# B45100557C.net
KiCad netlist of a schematic drawn in Altium Designer
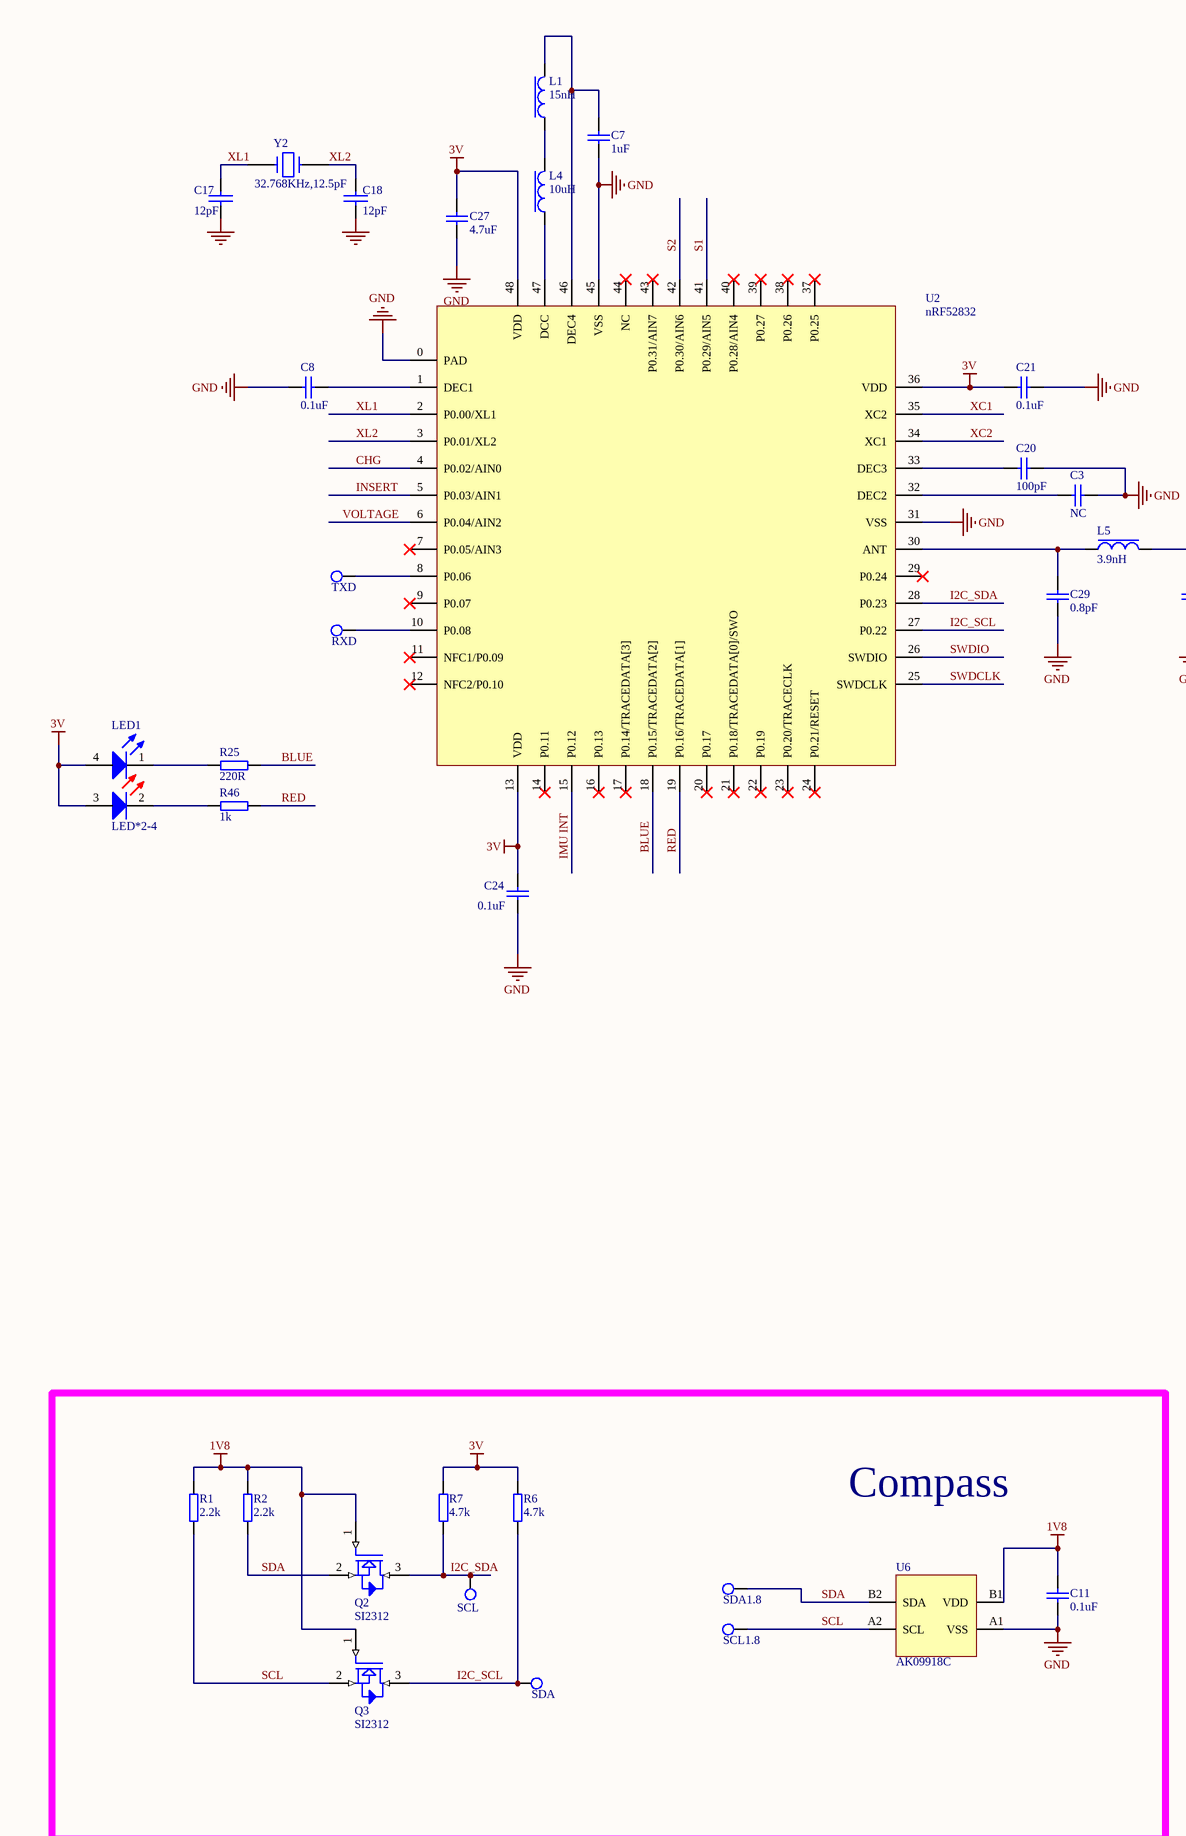
[diagram p0: B45100557C.SCHDOC, left]
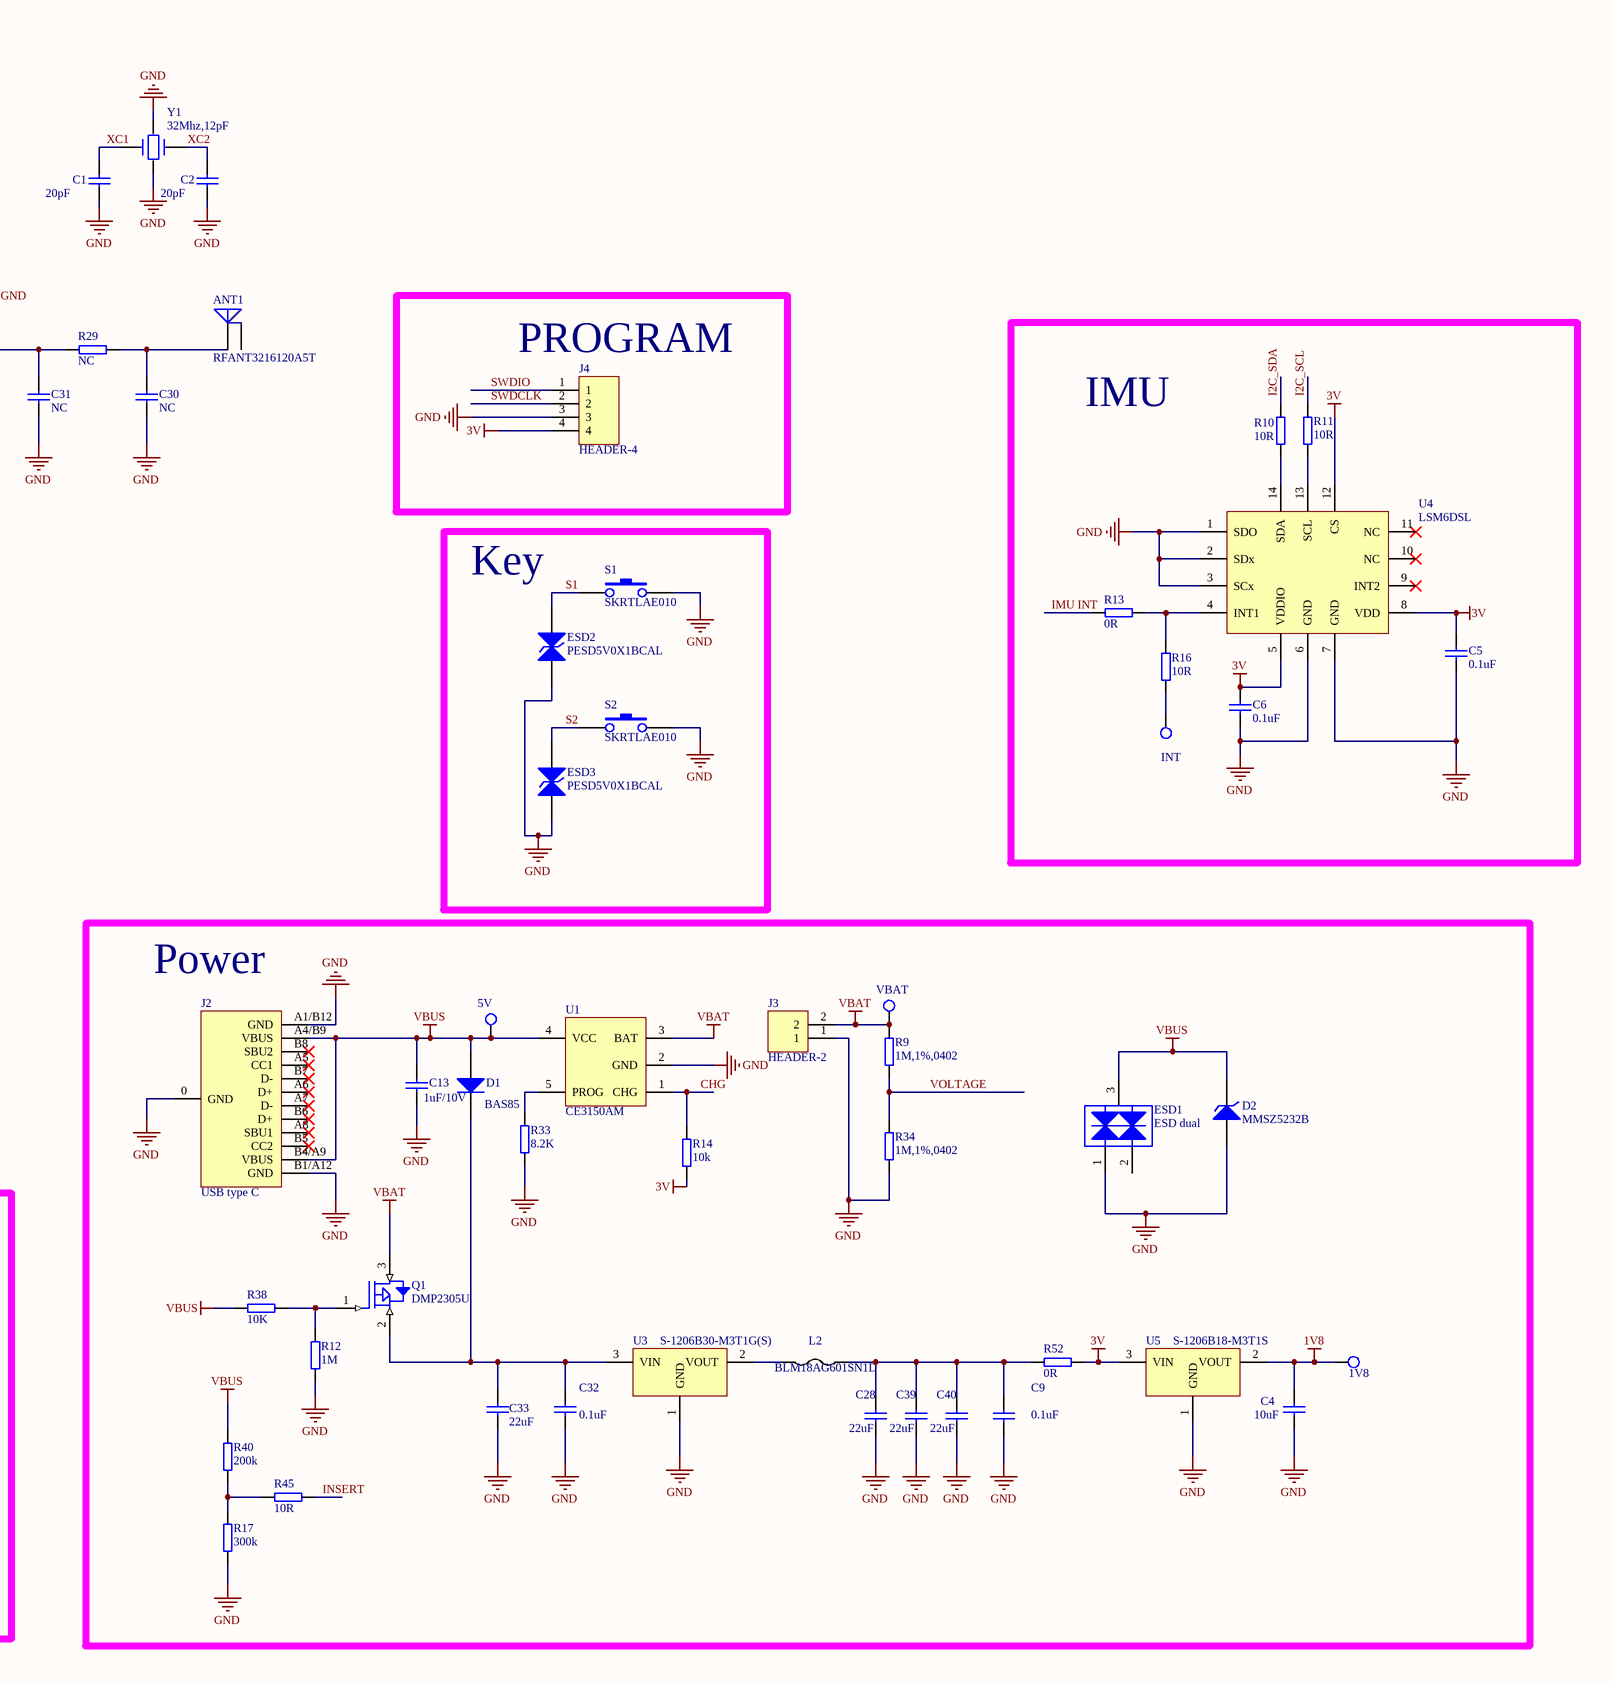
[diagram p1: B45100557C.SCHDOC, right]

(export (version "E")
  (design (tool "Eeschema 10.0.6"))
  (components
    (comp (ref "1V8") (value "TAP") (footprint "TS-1.0") (libsource (lib "dusun01-SCH") (part "TAP")))
    (comp (ref "5V") (value "TAP") (footprint "TS-1.0") (libsource (lib "dusun01-SCH") (part "TAP")))
    (comp (ref "ANT1")
      (value "RFANT3216120A5T")
      (footprint "RFANT3216120A1T")
      (libsource (lib "dusun01-SCH") (part "ANTENNA"))
    )
    (comp (ref "C1") (value "20pF") (footprint "C-0402") (libsource (lib "dusun01-SCH") (part "CAP")))
    (comp (ref "C2") (value "20pF") (footprint "C-0402") (libsource (lib "dusun01-SCH") (part "CAP")))
    (comp (ref "C3") (value "NC") (footprint "C-0402") (libsource (lib "dusun01-SCH") (part "CAP")))
    (comp (ref "C4") (value "10uF") (footprint "C-0603") (libsource (lib "dusun01-SCH") (part "CAP")))
    (comp (ref "C5")
      (value "0.1uF")
      (footprint "C-0402")
      (description "capacitor 27 pF NPO , +/- 2 %, SMD case 0603")
      (fields
        (field (name "MANUFACTURER") "Generic Components")
        (field (name "PUBLISHER") "Altium Hobart Technology Centre")
      )
      (libsource (lib "Miscellaneous Devices") (part "Cap"))
    )
    (comp (ref "C6")
      (value "0.1uF")
      (footprint "C-0402")
      (description "capacitor 27 pF NPO , +/- 2 %, SMD case 0603")
      (fields
        (field (name "MANUFACTURER") "Generic Components")
        (field (name "PUBLISHER") "Altium Hobart Technology Centre")
      )
      (libsource (lib "Miscellaneous Devices") (part "Cap"))
    )
    (comp (ref "C7") (value "1uF") (footprint "C-0402") (libsource (lib "dusun01-SCH") (part "CAP")))
    (comp (ref "C8") (value "0.1uF") (footprint "C-0402") (libsource (lib "dusun01-SCH") (part "CAP")))
    (comp (ref "C9") (value "0.1uF") (footprint "C-0402") (libsource (lib "dusun01-SCH") (part "CAP")))
    (comp (ref "C11")
      (value "0.1uF")
      (footprint "C-0402")
      (description "capacitor 27 pF NPO , +/- 2 %, SMD case 0603")
      (fields
        (field (name "MANUFACTURER") "Generic Components")
        (field (name "PUBLISHER") "Altium Hobart Technology Centre")
      )
      (libsource (lib "Miscellaneous Devices") (part "Cap"))
    )
    (comp (ref "C13") (value "1uF/10V") (footprint "C-0402") (libsource (lib "dusun01-SCH") (part "CAP")))
    (comp (ref "C17")
      (value "12pF")
      (footprint "dusun01-pcb:C-0402")
      (description "Capacitor")
      (libsource (lib "*") (part "CAP"))
    )
    (comp (ref "C18")
      (value "12pF")
      (footprint "dusun01-pcb:C-0402")
      (description "Capacitor")
      (libsource (lib "*") (part "CAP"))
    )
    (comp (ref "C20") (value "100pF") (footprint "C-0402") (libsource (lib "dusun01-SCH") (part "CAP")))
    (comp (ref "C21") (value "0.1uF") (footprint "C-0402") (libsource (lib "dusun01-SCH") (part "CAP")))
    (comp (ref "C24") (value "0.1uF") (footprint "C-0402") (libsource (lib "dusun01-SCH") (part "CAP")))
    (comp (ref "C27") (value "4.7uF") (footprint "C-0603") (libsource (lib "dusun01-SCH") (part "CAP")))
    (comp (ref "C28") (value "22uF") (footprint "C-0805") (libsource (lib "dusun01-SCH") (part "CAP")))
    (comp (ref "C29") (value "0.8pF") (footprint "C-0402") (libsource (lib "dusun01-SCH") (part "CAP")))
    (comp (ref "C30") (value "NC") (footprint "C-0402") (libsource (lib "dusun01-SCH") (part "CAP")))
    (comp (ref "C31") (value "NC") (footprint "C-0402") (libsource (lib "dusun01-SCH") (part "CAP")))
    (comp (ref "C32") (value "0.1uF") (footprint "C-0402") (libsource (lib "dusun01-SCH") (part "CAP")))
    (comp (ref "C33") (value "22uF") (footprint "dusun01-pcb:C-0805") (libsource (lib "") (part "CAP_1")))
    (comp (ref "C39") (value "22uF") (footprint "C-0805") (libsource (lib "dusun01-SCH") (part "CAP")))
    (comp (ref "C40") (value "22uF") (footprint "C-0805") (libsource (lib "dusun01-SCH") (part "CAP")))
    (comp (ref "D1") (value "BAS85") (footprint "SOD-80") (libsource (lib "dusun01-SCH") (part "DIODE")))
    (comp (ref "D2") (value "MMSZ5232B") (footprint "sod-123") (libsource (lib "dusun01-SCH") (part "ZENER")))
    (comp (ref "ESD1")
      (value "ESD dual")
      (footprint "SOT-23")
      (libsource (lib "dusun01-SCH") (part "ESD dual"))
    )
    (comp (ref "ESD2")
      (value "PESD5V0X1BCAL")
      (footprint "R-0402")
      (libsource (lib "dusun01-SCH") (part "ESD"))
    )
    (comp (ref "ESD3")
      (value "PESD5V0X1BCAL")
      (footprint "R-0402")
      (libsource (lib "dusun01-SCH") (part "ESD"))
    )
    (comp (ref "INT") (value "TAP") (footprint "TS-1.0") (libsource (lib "dusun01-SCH") (part "TAP")))
    (comp (ref "J2")
      (value "USB type C")
      (footprint "USB type C")
      (libsource (lib "dusun01-SCH") (part "USB type C"))
    )
    (comp (ref "J3")
      (value "HEADER-2")
      (footprint "1.25T-2AWB")
      (libsource (lib "dusun01-SCH") (part "HEADER-2"))
    )
    (comp (ref "J4")
      (value "HEADER-4")
      (footprint "PH-4-2.54-1")
      (libsource (lib "dusun01-SCH") (part "HEADER-4"))
    )
    (comp (ref "L1") (value "15nH") (footprint "R-0402") (libsource (lib "dusun01-SCH") (part "INDUCTOR")))
    (comp (ref "L2")
      (value "BLM18AG601SN1D")
      (footprint "dusun01-pcb:R-0603")
      (libsource (lib "*") (part "Inductance"))
    )
    (comp (ref "L4")
      (value "10uH")
      (footprint "dusun02-pcb:R-0805")
      (libsource (lib "dusun01-SCH") (part "INDUCTOR"))
    )
    (comp (ref "L5") (value "3.9nH") (footprint "R-0402") (libsource (lib "dusun01-SCH") (part "INDUCTOR")))
    (comp (ref "LED1")
      (value "LED*2-4")
      (footprint "A-SP1942R6B1C-A01-2T")
      (libsource (lib "dusun01-SCH") (part "LED*2-4"))
    )
    (comp (ref "Q1")
      (value "DMP2305U")
      (footprint "SOT-23")
      (libsource (lib "dusun01-SCH") (part "MOSFET P"))
    )
    (comp (ref "Q2") (value "SI2312") (footprint "SOT-23") (libsource (lib "dusun01-SCH") (part "MOSFET N")))
    (comp (ref "Q3") (value "SI2312") (footprint "SOT-23") (libsource (lib "dusun01-SCH") (part "MOSFET N")))
    (comp (ref "R1") (value "2.2k") (footprint "R-0402") (libsource (lib "dusun01-SCH") (part "RES")))
    (comp (ref "R2") (value "2.2k") (footprint "R-0402") (libsource (lib "dusun01-SCH") (part "RES")))
    (comp (ref "R6") (value "4.7k") (footprint "R-0402") (libsource (lib "dusun01-SCH") (part "RES")))
    (comp (ref "R7") (value "4.7k") (footprint "R-0402") (libsource (lib "dusun01-SCH") (part "RES")))
    (comp (ref "R9") (value "1M,1%,0402") (footprint "R-0402") (libsource (lib "dusun01-SCH") (part "RES")))
    (comp (ref "R10") (value "10R") (footprint "R-0402") (libsource (lib "dusun01-SCH") (part "RES")))
    (comp (ref "R11") (value "10R") (footprint "R-0402") (libsource (lib "dusun01-SCH") (part "RES")))
    (comp (ref "R12") (value "1M") (footprint "R-0402") (libsource (lib "dusun01-SCH") (part "RES")))
    (comp (ref "R13") (value "0R") (footprint "R-0402") (libsource (lib "dusun01-SCH") (part "RES")))
    (comp (ref "R14") (value "10k") (footprint "R-0402") (libsource (lib "dusun01-SCH") (part "RES")))
    (comp (ref "R16") (value "10R") (footprint "R-0402") (libsource (lib "dusun01-SCH") (part "RES")))
    (comp (ref "R17") (value "300k") (footprint "R-0402") (libsource (lib "dusun01-SCH") (part "RES")))
    (comp (ref "R25") (value "220R") (footprint "R-0402") (libsource (lib "dusun01-SCH") (part "RES")))
    (comp (ref "R29") (value "NC") (footprint "R-0402") (libsource (lib "dusun01-SCH") (part "RES")))
    (comp (ref "R33") (value "8.2K") (footprint "R-0402") (libsource (lib "dusun01-SCH") (part "RES")))
    (comp (ref "R34") (value "1M,1%,0402") (footprint "R-0402") (libsource (lib "dusun01-SCH") (part "RES")))
    (comp (ref "R38") (value "10K") (footprint "R-0402") (libsource (lib "dusun01-SCH") (part "RES")))
    (comp (ref "R40") (value "200k") (footprint "R-0402") (libsource (lib "dusun01-SCH") (part "RES")))
    (comp (ref "R45") (value "10R") (footprint "R-0402") (libsource (lib "dusun01-SCH") (part "RES")))
    (comp (ref "R46") (value "1k") (footprint "R-0402") (libsource (lib "dusun01-SCH") (part "RES")))
    (comp (ref "R52") (value "0R") (footprint "R-0603") (libsource (lib "dusun01-SCH") (part "RES")))
    (comp (ref "RXD") (value "TAP") (footprint "TS-1.0") (libsource (lib "dusun01-SCH") (part "TAP")))
    (comp (ref "S1") (value "SKRTLAE010") (footprint "SKRTLAE010") (libsource (lib "dusun") (part "SW-PB")))
    (comp (ref "S2") (value "SKRTLAE010") (footprint "SKRTLAE010") (libsource (lib "dusun") (part "SW-PB")))
    (comp (ref "SCL") (value "TAP") (footprint "TS-1.0") (libsource (lib "dusun01-SCH") (part "TAP")))
    (comp (ref "SCL1.8") (value "TAP") (footprint "TS-1.0") (libsource (lib "dusun01-SCH") (part "TAP")))
    (comp (ref "SDA") (value "TAP") (footprint "TS-1.0") (libsource (lib "dusun01-SCH") (part "TAP")))
    (comp (ref "SDA1.8") (value "TAP") (footprint "TS-1.0") (libsource (lib "dusun01-SCH") (part "TAP")))
    (comp (ref "TXD") (value "TAP") (footprint "TS-1.0") (libsource (lib "dusun01-SCH") (part "TAP")))
    (comp (ref "U1")
      (value "CE3150AM")
      (footprint "SOT-23-5")
      (libsource (lib "dusun01-SCH") (part "CE3150AM"))
    )
    (comp (ref "U2")
      (value "nRF52832")
      (footprint "QFN-48-6*6-0.4")
      (libsource (lib "dusun01-SCH") (part "nRF52832"))
    )
    (comp (ref "U3")
      (value "S-1206B30-M3T1G(S)")
      (footprint "SOT-23")
      (libsource (lib "dusun01-SCH") (part "S-1206BXX"))
    )
    (comp (ref "U4") (value "LSM6DSL") (footprint "LGA14") (libsource (lib "dusun01-SCH") (part "LSM6DSL")))
    (comp (ref "U5")
      (value "S-1206B18-M3T1S")
      (footprint "SOT-23")
      (libsource (lib "dusun01-SCH") (part "S-1206BXX"))
    )
    (comp (ref "U6")
      (value "AK09918C")
      (footprint "AK09918C")
      (libsource (lib "dusun01-SCH") (part "AK09918C"))
    )
    (comp (ref "VBAT") (value "TAP") (footprint "TS-1.0") (libsource (lib "dusun01-SCH") (part "TAP")))
    (comp (ref "Y1")
      (value "32Mhz,12pF")
      (footprint "XD3225-1-12M-125M")
      (libsource (lib "dusun01-SCH") (part "CRYSTAL4"))
    )
    (comp (ref "Y2")
      (value "32.768KHz,12.5pF")
      (footprint "32.768Khz-3215")
      (libsource (lib "dusun01-SCH") (part "CRYSTAL2"))
    )
  )
  (nets
    (net (code "1") (name "/BLUE") (class "Default")
      (node (ref "R25") (pin "1") (pinfunction "1_1") (pintype "passive"))
      (node (ref "U2") (pin "18") (pinfunction "P0.15/TRACEDATA[2]_18") (pintype "passive"))
    )
    (net (code "2") (name "/CHG") (class "Default")
      (node (ref "R14") (pin "2") (pinfunction "2_2") (pintype "passive"))
      (node (ref "U1") (pin "1") (pinfunction "CHG_1") (pintype "passive"))
      (node (ref "U2") (pin "4") (pinfunction "P0.02/AIN0_4") (pintype "passive"))
    )
    (net (code "3") (name "/I2C_SCL") (class "Default")
      (node (ref "Q3") (pin "3") (pinfunction "D_3") (pintype "input"))
      (node (ref "R11") (pin "2") (pinfunction "2_2") (pintype "passive"))
      (node (ref "R6") (pin "2") (pinfunction "2_2") (pintype "passive"))
      (node (ref "SDA") (pin "1") (pinfunction "1_1") (pintype "passive"))
      (node (ref "U2") (pin "27") (pinfunction "P0.22_27") (pintype "passive"))
    )
    (net (code "4") (name "/I2C_SDA") (class "Default")
      (node (ref "Q2") (pin "3") (pinfunction "D_3") (pintype "input"))
      (node (ref "R10") (pin "2") (pinfunction "2_2") (pintype "passive"))
      (node (ref "R7") (pin "2") (pinfunction "2_2") (pintype "passive"))
      (node (ref "SCL") (pin "1") (pinfunction "1_1") (pintype "passive"))
      (node (ref "U2") (pin "28") (pinfunction "P0.23_28") (pintype "passive"))
    )
    (net (code "5") (name "/IMU INT") (class "Default")
      (node (ref "R13") (pin "1") (pinfunction "1_1") (pintype "passive"))
      (node (ref "U2") (pin "15") (pinfunction "P0.12_15") (pintype "passive"))
    )
    (net (code "6") (name "/INSERT") (class "Default")
      (node (ref "R45") (pin "1") (pinfunction "1_1") (pintype "passive"))
      (node (ref "U2") (pin "5") (pinfunction "P0.03/AIN1_5") (pintype "passive"))
    )
    (net (code "7") (name "/RED") (class "Default")
      (node (ref "R46") (pin "1") (pinfunction "1_1") (pintype "passive"))
      (node (ref "U2") (pin "19") (pinfunction "P0.16/TRACEDATA[1]_19") (pintype "passive"))
    )
    (net (code "8") (name "/S1") (class "Default")
      (node (ref "ESD2") (pin "2") (pinfunction "2_2") (pintype "passive"))
      (node (ref "S1") (pin "2") (pinfunction "2_2") (pintype "passive"))
      (node (ref "U2") (pin "41") (pinfunction "P0.29/AIN5_41") (pintype "passive"))
    )
    (net (code "9") (name "/S2") (class "Default")
      (node (ref "ESD3") (pin "2") (pinfunction "2_2") (pintype "passive"))
      (node (ref "S2") (pin "2") (pinfunction "2_2") (pintype "passive"))
      (node (ref "U2") (pin "42") (pinfunction "P0.30/AIN6_42") (pintype "passive"))
    )
    (net (code "10") (name "/SCL") (class "Default")
      (node (ref "Q3") (pin "2") (pinfunction "S_2") (pintype "input"))
      (node (ref "R1") (pin "2") (pinfunction "2_2") (pintype "passive"))
      (node (ref "SCL1.8") (pin "1") (pinfunction "1_1") (pintype "passive"))
      (node (ref "U6") (pin "A2") (pinfunction "SCL_A2") (pintype "passive"))
    )
    (net (code "11") (name "/SDA") (class "Default")
      (node (ref "Q2") (pin "2") (pinfunction "S_2") (pintype "input"))
      (node (ref "R2") (pin "2") (pinfunction "2_2") (pintype "passive"))
      (node (ref "SDA1.8") (pin "1") (pinfunction "1_1") (pintype "passive"))
      (node (ref "U6") (pin "B2") (pinfunction "SDA_B2") (pintype "passive"))
    )
    (net (code "12") (name "/SWDCLK") (class "Default")
      (node (ref "J4") (pin "2") (pinfunction "2_2") (pintype "passive"))
      (node (ref "U2") (pin "25") (pinfunction "SWDCLK_25") (pintype "passive"))
    )
    (net (code "13") (name "/SWDIO") (class "Default")
      (node (ref "J4") (pin "1") (pinfunction "1_1") (pintype "passive"))
      (node (ref "U2") (pin "26") (pinfunction "SWDIO_26") (pintype "passive"))
    )
    (net (code "14") (name "/VOLTAGE") (class "Default")
      (node (ref "R34") (pin "2") (pinfunction "2_2") (pintype "passive"))
      (node (ref "R9") (pin "1") (pinfunction "1_1") (pintype "passive"))
      (node (ref "U2") (pin "6") (pinfunction "P0.04/AIN2_6") (pintype "passive"))
    )
    (net (code "15") (name "/XC1") (class "Default")
      (node (ref "C1") (pin "1") (pinfunction "1_1") (pintype "passive"))
      (node (ref "U2") (pin "35") (pinfunction "XC2_35") (pintype "passive"))
      (node (ref "Y1") (pin "1") (pinfunction "1_1") (pintype "passive"))
    )
    (net (code "16") (name "/XC2") (class "Default")
      (node (ref "C2") (pin "1") (pinfunction "1_1") (pintype "passive"))
      (node (ref "U2") (pin "34") (pinfunction "XC1_34") (pintype "passive"))
      (node (ref "Y1") (pin "2") (pinfunction "2_2") (pintype "passive"))
    )
    (net (code "17") (name "/XL1") (class "Default")
      (node (ref "C17") (pin "1") (pinfunction "1_1") (pintype "passive"))
      (node (ref "U2") (pin "2") (pinfunction "P0.00/XL1_2") (pintype "passive"))
      (node (ref "Y2") (pin "1") (pinfunction "1_1") (pintype "passive"))
    )
    (net (code "18") (name "/XL2") (class "Default")
      (node (ref "C18") (pin "1") (pinfunction "1_1") (pintype "passive"))
      (node (ref "U2") (pin "3") (pinfunction "P0.01/XL2_3") (pintype "passive"))
      (node (ref "Y2") (pin "2") (pinfunction "2_2") (pintype "passive"))
    )
    (net (code "19") (name "1V8") (class "Default")
      (node (ref "1V8") (pin "1") (pinfunction "1_1") (pintype "passive"))
      (node (ref "C11") (pin "1") (pinfunction "1_1") (pintype "passive"))
      (node (ref "C4") (pin "1") (pinfunction "1_1") (pintype "passive"))
      (node (ref "Q2") (pin "1") (pinfunction "G_1") (pintype "input"))
      (node (ref "Q3") (pin "1") (pinfunction "G_1") (pintype "input"))
      (node (ref "R1") (pin "1") (pinfunction "1_1") (pintype "passive"))
      (node (ref "R2") (pin "1") (pinfunction "1_1") (pintype "passive"))
      (node (ref "U5") (pin "2") (pinfunction "VOUT_2") (pintype "passive"))
      (node (ref "U6") (pin "B1") (pinfunction "VDD_B1") (pintype "passive"))
    )
    (net (code "20") (name "3V") (class "Default")
      (node (ref "C21") (pin "1") (pinfunction "1_1") (pintype "passive"))
      (node (ref "C24") (pin "1") (pinfunction "1_1") (pintype "passive"))
      (node (ref "C27") (pin "1") (pinfunction "1_1") (pintype "passive"))
      (node (ref "C5") (pin "1") (pinfunction "1_1") (pintype "passive"))
      (node (ref "C6") (pin "1") (pinfunction "1_1") (pintype "passive"))
      (node (ref "J4") (pin "4") (pinfunction "4_4") (pintype "passive"))
      (node (ref "LED1") (pin "3") (pinfunction "3_3") (pintype "passive"))
      (node (ref "LED1") (pin "4") (pinfunction "4_4") (pintype "passive"))
      (node (ref "R14") (pin "1") (pinfunction "1_1") (pintype "passive"))
      (node (ref "R52") (pin "1") (pinfunction "1_1") (pintype "passive"))
      (node (ref "R6") (pin "1") (pinfunction "1_1") (pintype "passive"))
      (node (ref "R7") (pin "1") (pinfunction "1_1") (pintype "passive"))
      (node (ref "U2") (pin "13") (pinfunction "VDD_13") (pintype "passive"))
      (node (ref "U2") (pin "36") (pinfunction "VDD_36") (pintype "passive"))
      (node (ref "U2") (pin "48") (pinfunction "VDD_48") (pintype "passive"))
      (node (ref "U4") (pin "12") (pinfunction "CS_12") (pintype "passive"))
      (node (ref "U4") (pin "5") (pinfunction "VDDIO_5") (pintype "passive"))
      (node (ref "U4") (pin "8") (pinfunction "VDD_8") (pintype "passive"))
      (node (ref "U5") (pin "3") (pinfunction "VIN_3") (pintype "passive"))
    )
    (net (code "21") (name "GND") (class "Default")
      (node (ref "C1") (pin "2") (pinfunction "2_2") (pintype "passive"))
      (node (ref "C11") (pin "2") (pinfunction "2_2") (pintype "passive"))
      (node (ref "C13") (pin "2") (pinfunction "2_2") (pintype "passive"))
      (node (ref "C17") (pin "2") (pinfunction "2_2") (pintype "passive"))
      (node (ref "C18") (pin "2") (pinfunction "2_2") (pintype "passive"))
      (node (ref "C2") (pin "2") (pinfunction "2_2") (pintype "passive"))
      (node (ref "C20") (pin "2") (pinfunction "2_2") (pintype "passive"))
      (node (ref "C21") (pin "2") (pinfunction "2_2") (pintype "passive"))
      (node (ref "C24") (pin "2") (pinfunction "2_2") (pintype "passive"))
      (node (ref "C27") (pin "2") (pinfunction "2_2") (pintype "passive"))
      (node (ref "C28") (pin "2") (pinfunction "2_2") (pintype "passive"))
      (node (ref "C29") (pin "2") (pinfunction "2_2") (pintype "passive"))
      (node (ref "C3") (pin "2") (pinfunction "2_2") (pintype "passive"))
      (node (ref "C30") (pin "2") (pinfunction "2_2") (pintype "passive"))
      (node (ref "C31") (pin "2") (pinfunction "2_2") (pintype "passive"))
      (node (ref "C32") (pin "2") (pinfunction "2_2") (pintype "passive"))
      (node (ref "C33") (pin "2") (pinfunction "2_2") (pintype "passive"))
      (node (ref "C39") (pin "2") (pinfunction "2_2") (pintype "passive"))
      (node (ref "C4") (pin "2") (pinfunction "2_2") (pintype "passive"))
      (node (ref "C40") (pin "2") (pinfunction "2_2") (pintype "passive"))
      (node (ref "C5") (pin "2") (pinfunction "2_2") (pintype "passive"))
      (node (ref "C6") (pin "2") (pinfunction "2_2") (pintype "passive"))
      (node (ref "C7") (pin "1") (pinfunction "1_1") (pintype "passive"))
      (node (ref "C8") (pin "1") (pinfunction "1_1") (pintype "passive"))
      (node (ref "C9") (pin "2") (pinfunction "2_2") (pintype "passive"))
      (node (ref "D2") (pin "1") (pinfunction "1_1") (pintype "passive"))
      (node (ref "ESD1") (pin "1") (pinfunction "1_1") (pintype "passive"))
      (node (ref "ESD2") (pin "1") (pinfunction "1_1") (pintype "passive"))
      (node (ref "ESD3") (pin "1") (pinfunction "1_1") (pintype "passive"))
      (node (ref "J2") (pin "0") (pinfunction "GND_0") (pintype "passive"))
      (node (ref "J2") (pin "A1/B12") (pinfunction "GND_A1/B12") (pintype "passive"))
      (node (ref "J2") (pin "B1/A12") (pinfunction "GND_B1/A12") (pintype "passive"))
      (node (ref "J3") (pin "1") (pinfunction "1_1") (pintype "passive"))
      (node (ref "J4") (pin "3") (pinfunction "3_3") (pintype "passive"))
      (node (ref "R12") (pin "1") (pinfunction "1_1") (pintype "passive"))
      (node (ref "R17") (pin "1") (pinfunction "1_1") (pintype "passive"))
      (node (ref "R33") (pin "1") (pinfunction "1_1") (pintype "passive"))
      (node (ref "R34") (pin "1") (pinfunction "1_1") (pintype "passive"))
      (node (ref "S1") (pin "1") (pinfunction "1_1") (pintype "passive"))
      (node (ref "S2") (pin "1") (pinfunction "1_1") (pintype "passive"))
      (node (ref "U1") (pin "2") (pinfunction "GND_2") (pintype "passive"))
      (node (ref "U2") (pin "0") (pinfunction "PAD_0") (pintype "passive"))
      (node (ref "U2") (pin "31") (pinfunction "VSS_31") (pintype "passive"))
      (node (ref "U2") (pin "45") (pinfunction "VSS_45") (pintype "passive"))
      (node (ref "U3") (pin "1") (pinfunction "GND_1") (pintype "passive"))
      (node (ref "U4") (pin "1") (pinfunction "SDO_1") (pintype "passive"))
      (node (ref "U4") (pin "2") (pinfunction "SDx_2") (pintype "passive"))
      (node (ref "U4") (pin "3") (pinfunction "SCx_3") (pintype "passive"))
      (node (ref "U4") (pin "6") (pinfunction "GND_6") (pintype "passive"))
      (node (ref "U4") (pin "7") (pinfunction "GND_7") (pintype "passive"))
      (node (ref "U5") (pin "1") (pinfunction "GND_1") (pintype "passive"))
      (node (ref "U6") (pin "A1") (pinfunction "VSS_A1") (pintype "passive"))
      (node (ref "Y1") (pin "3") (pinfunction "3_3") (pintype "passive"))
    )
    (net (code "22") (name "Net-(ANT1-Pad1)") (class "Default")
      (node (ref "ANT1") (pin "1") (pinfunction "1_1") (pintype "passive"))
      (node (ref "C30") (pin "1") (pinfunction "1_1") (pintype "passive"))
      (node (ref "R29") (pin "2") (pinfunction "2_2") (pintype "passive"))
    )
    (net (code "23") (name "Net-(C28-Pad1)") (class "Default")
      (node (ref "C28") (pin "1") (pinfunction "1_1") (pintype "passive"))
      (node (ref "C39") (pin "1") (pinfunction "1_1") (pintype "passive"))
      (node (ref "C40") (pin "1") (pinfunction "1_1") (pintype "passive"))
      (node (ref "C9") (pin "1") (pinfunction "1_1") (pintype "passive"))
      (node (ref "L2") (pin "1") (pintype "passive"))
      (node (ref "R52") (pin "2") (pinfunction "2_2") (pintype "passive"))
    )
    (net (code "24") (name "Net-(C31-Pad1)") (class "Default")
      (node (ref "C31") (pin "1") (pinfunction "1_1") (pintype "passive"))
      (node (ref "L5") (pin "2") (pinfunction "2_2") (pintype "passive"))
      (node (ref "R29") (pin "1") (pinfunction "1_1") (pintype "passive"))
    )
    (net (code "25") (name "Net-(INT-Pad1)") (class "Default")
      (node (ref "INT") (pin "1") (pinfunction "1_1") (pintype "passive"))
      (node (ref "R16") (pin "1") (pinfunction "1_1") (pintype "passive"))
    )
    (net (code "26") (name "Net-(L1-Pad1)") (class "Default")
      (node (ref "L1") (pin "1") (pinfunction "1_1") (pintype "passive"))
      (node (ref "L4") (pin "2") (pinfunction "2_2") (pintype "passive"))
    )
    (net (code "27") (name "Net-(LED1-Pad1)") (class "Default")
      (node (ref "LED1") (pin "1") (pinfunction "1_1") (pintype "passive"))
      (node (ref "R25") (pin "2") (pinfunction "2_2") (pintype "passive"))
    )
    (net (code "28") (name "Net-(LED1-Pad2)") (class "Default")
      (node (ref "LED1") (pin "2") (pinfunction "2_2") (pintype "passive"))
      (node (ref "R46") (pin "2") (pinfunction "2_2") (pintype "passive"))
    )
    (net (code "29") (name "Net-(Q1-G)") (class "Default")
      (node (ref "Q1") (pin "1") (pinfunction "G_1") (pintype "input"))
      (node (ref "R12") (pin "2") (pinfunction "2_2") (pintype "passive"))
      (node (ref "R38") (pin "1") (pinfunction "1_1") (pintype "passive"))
    )
    (net (code "30") (name "Net-(Q1-S)") (class "Default")
      (node (ref "C32") (pin "1") (pinfunction "1_1") (pintype "passive"))
      (node (ref "C33") (pin "1") (pinfunction "1_1") (pintype "passive"))
      (node (ref "D1") (pin "2") (pinfunction "2_2") (pintype "passive"))
      (node (ref "Q1") (pin "2") (pinfunction "S_2") (pintype "input"))
      (node (ref "U3") (pin "3") (pinfunction "VIN_3") (pintype "passive"))
    )
    (net (code "31") (name "Net-(R17-Pad2)") (class "Default")
      (node (ref "R17") (pin "2") (pinfunction "2_2") (pintype "passive"))
      (node (ref "R40") (pin "1") (pinfunction "1_1") (pintype "passive"))
      (node (ref "R45") (pin "2") (pinfunction "2_2") (pintype "passive"))
    )
    (net (code "32") (name "Net-(U1-PROG)") (class "Default")
      (node (ref "R33") (pin "2") (pinfunction "2_2") (pintype "passive"))
      (node (ref "U1") (pin "5") (pinfunction "PROG_5") (pintype "passive"))
    )
    (net (code "33") (name "Net-(U2-ANT)") (class "Default")
      (node (ref "C29") (pin "1") (pinfunction "1_1") (pintype "passive"))
      (node (ref "L5") (pin "1") (pinfunction "1_1") (pintype "passive"))
      (node (ref "U2") (pin "30") (pinfunction "ANT_30") (pintype "passive"))
    )
    (net (code "34") (name "Net-(U2-DCC)") (class "Default")
      (node (ref "L4") (pin "1") (pinfunction "1_1") (pintype "passive"))
      (node (ref "U2") (pin "47") (pinfunction "DCC_47") (pintype "passive"))
    )
    (net (code "35") (name "Net-(U2-DEC1)") (class "Default")
      (node (ref "C8") (pin "2") (pinfunction "2_2") (pintype "passive"))
      (node (ref "U2") (pin "1") (pinfunction "DEC1_1") (pintype "passive"))
    )
    (net (code "36") (name "Net-(U2-DEC2)") (class "Default")
      (node (ref "C3") (pin "1") (pinfunction "1_1") (pintype "passive"))
      (node (ref "U2") (pin "32") (pinfunction "DEC2_32") (pintype "passive"))
    )
    (net (code "37") (name "Net-(U2-DEC3)") (class "Default")
      (node (ref "C20") (pin "1") (pinfunction "1_1") (pintype "passive"))
      (node (ref "U2") (pin "33") (pinfunction "DEC3_33") (pintype "passive"))
    )
    (net (code "38") (name "Net-(U2-DEC4)") (class "Default")
      (node (ref "C7") (pin "2") (pinfunction "2_2") (pintype "passive"))
      (node (ref "L1") (pin "2") (pinfunction "2_2") (pintype "passive"))
      (node (ref "U2") (pin "46") (pinfunction "DEC4_46") (pintype "passive"))
    )
    (net (code "39") (name "Net-(U2-P0.06)") (class "Default")
      (node (ref "TXD") (pin "1") (pinfunction "1_1") (pintype "passive"))
      (node (ref "U2") (pin "8") (pinfunction "P0.06_8") (pintype "passive"))
    )
    (net (code "40") (name "Net-(U2-P0.08)") (class "Default")
      (node (ref "RXD") (pin "1") (pinfunction "1_1") (pintype "passive"))
      (node (ref "U2") (pin "10") (pinfunction "P0.08_10") (pintype "passive"))
    )
    (net (code "41") (name "Net-(U3-VOUT)") (class "Default")
      (node (ref "L2") (pin "2") (pintype "passive"))
      (node (ref "U3") (pin "2") (pinfunction "VOUT_2") (pintype "passive"))
    )
    (net (code "42") (name "Net-(U4-INT1)") (class "Default")
      (node (ref "R13") (pin "2") (pinfunction "2_2") (pintype "passive"))
      (node (ref "R16") (pin "2") (pinfunction "2_2") (pintype "passive"))
      (node (ref "U4") (pin "4") (pinfunction "INT1_4") (pintype "passive"))
    )
    (net (code "43") (name "Net-(U4-SCL)") (class "Default")
      (node (ref "R11") (pin "1") (pinfunction "1_1") (pintype "passive"))
      (node (ref "U4") (pin "13") (pinfunction "SCL_13") (pintype "passive"))
    )
    (net (code "44") (name "Net-(U4-SDA)") (class "Default")
      (node (ref "R10") (pin "1") (pinfunction "1_1") (pintype "passive"))
      (node (ref "U4") (pin "14") (pinfunction "SDA_14") (pintype "passive"))
    )
    (net (code "45") (name "VBAT") (class "Default")
      (node (ref "J3") (pin "2") (pinfunction "2_2") (pintype "passive"))
      (node (ref "Q1") (pin "3") (pinfunction "D_3") (pintype "input"))
      (node (ref "R9") (pin "2") (pinfunction "2_2") (pintype "passive"))
      (node (ref "U1") (pin "3") (pinfunction "BAT_3") (pintype "passive"))
      (node (ref "VBAT") (pin "1") (pinfunction "1_1") (pintype "passive"))
    )
    (net (code "46") (name "VBUS") (class "Default")
      (node (ref "5V") (pin "1") (pinfunction "1_1") (pintype "passive"))
      (node (ref "C13") (pin "1") (pinfunction "1_1") (pintype "passive"))
      (node (ref "D1") (pin "1") (pinfunction "1_1") (pintype "passive"))
      (node (ref "D2") (pin "2") (pinfunction "2_2") (pintype "passive"))
      (node (ref "ESD1") (pin "3") (pinfunction "3_3") (pintype "passive"))
      (node (ref "J2") (pin "A4/B9") (pinfunction "VBUS_A4/B9") (pintype "passive"))
      (node (ref "J2") (pin "B4/A9") (pinfunction "VBUS_B4/A9") (pintype "passive"))
      (node (ref "R38") (pin "2") (pinfunction "2_2") (pintype "passive"))
      (node (ref "R40") (pin "2") (pinfunction "2_2") (pintype "passive"))
      (node (ref "U1") (pin "4") (pinfunction "VCC_4") (pintype "passive"))
    )
    (net (code "47") (name "unconnected-(ANT1-Pad2)") (class "Default")
      (node (ref "ANT1") (pin "2") (pinfunction "2_2") (pintype "passive"))
    )
    (net (code "48") (name "unconnected-(ESD1-Pad2)") (class "Default")
      (node (ref "ESD1") (pin "2") (pinfunction "2_2") (pintype "passive"))
    )
    (net (code "49") (name "unconnected-(J2-CC1-PadA5)") (class "Default")
      (node (ref "J2") (pin "A5") (pinfunction "CC1_A5") (pintype "passive+no_connect"))
    )
    (net (code "50") (name "unconnected-(J2-CC2-PadB5)") (class "Default")
      (node (ref "J2") (pin "B5") (pinfunction "CC2_B5") (pintype "passive+no_connect"))
    )
    (net (code "51") (name "unconnected-(J2-D+-PadA6)") (class "Default")
      (node (ref "J2") (pin "A6") (pinfunction "D+_A6") (pintype "passive+no_connect"))
    )
    (net (code "52") (name "unconnected-(J2-D+-PadB6)") (class "Default")
      (node (ref "J2") (pin "B6") (pinfunction "D+_B6") (pintype "passive+no_connect"))
    )
    (net (code "53") (name "unconnected-(J2-D--PadA7)") (class "Default")
      (node (ref "J2") (pin "A7") (pinfunction "D-_A7") (pintype "passive+no_connect"))
    )
    (net (code "54") (name "unconnected-(J2-D--PadB7)") (class "Default")
      (node (ref "J2") (pin "B7") (pinfunction "D-_B7") (pintype "passive+no_connect"))
    )
    (net (code "55") (name "unconnected-(J2-SBU1-PadA8)") (class "Default")
      (node (ref "J2") (pin "A8") (pinfunction "SBU1_A8") (pintype "passive+no_connect"))
    )
    (net (code "56") (name "unconnected-(J2-SBU2-PadB8)") (class "Default")
      (node (ref "J2") (pin "B8") (pinfunction "SBU2_B8") (pintype "passive+no_connect"))
    )
    (net (code "57") (name "unconnected-(U2-NC-Pad44)") (class "Default")
      (node (ref "U2") (pin "44") (pinfunction "NC_44") (pintype "passive+no_connect"))
    )
    (net (code "58") (name "unconnected-(U2-NFC1{slash}P0.09-Pad11)") (class "Default")
      (node (ref "U2") (pin "11") (pinfunction "NFC1/P0.09_11") (pintype "passive+no_connect"))
    )
    (net (code "59") (name "unconnected-(U2-NFC2{slash}P0.10-Pad12)") (class "Default")
      (node (ref "U2") (pin "12") (pinfunction "NFC2/P0.10_12") (pintype "passive+no_connect"))
    )
    (net (code "60") (name "unconnected-(U2-P0.05{slash}AIN3-Pad7)") (class "Default")
      (node (ref "U2") (pin "7") (pinfunction "P0.05/AIN3_7") (pintype "passive+no_connect"))
    )
    (net (code "61") (name "unconnected-(U2-P0.07-Pad9)") (class "Default")
      (node (ref "U2") (pin "9") (pinfunction "P0.07_9") (pintype "passive+no_connect"))
    )
    (net (code "62") (name "unconnected-(U2-P0.11-Pad14)") (class "Default")
      (node (ref "U2") (pin "14") (pinfunction "P0.11_14") (pintype "passive+no_connect"))
    )
    (net (code "63") (name "unconnected-(U2-P0.13-Pad16)") (class "Default")
      (node (ref "U2") (pin "16") (pinfunction "P0.13_16") (pintype "passive+no_connect"))
    )
    (net (code "64") (name "unconnected-(U2-P0.14{slash}TRACEDATA[3]-Pad17)") (class "Default")
      (node (ref "U2") (pin "17") (pinfunction "P0.14/TRACEDATA[3]_17") (pintype "passive+no_connect"))
    )
    (net (code "65") (name "unconnected-(U2-P0.17-Pad20)") (class "Default")
      (node (ref "U2") (pin "20") (pinfunction "P0.17_20") (pintype "passive+no_connect"))
    )
    (net (code "66") (name "unconnected-(U2-P0.18{slash}TRACEDATA[0]{slash}SWO-Pad21)") (class "Default")
      (node (ref "U2") (pin "21") (pinfunction "P0.18/TRACEDATA[0]/SWO_21") (pintype "passive+no_connect"))
    )
    (net (code "67") (name "unconnected-(U2-P0.19-Pad22)") (class "Default")
      (node (ref "U2") (pin "22") (pinfunction "P0.19_22") (pintype "passive+no_connect"))
    )
    (net (code "68") (name "unconnected-(U2-P0.20{slash}TRACECLK-Pad23)") (class "Default")
      (node (ref "U2") (pin "23") (pinfunction "P0.20/TRACECLK_23") (pintype "passive+no_connect"))
    )
    (net (code "69") (name "unconnected-(U2-P0.21{slash}RESET-Pad24)") (class "Default")
      (node (ref "U2") (pin "24") (pinfunction "P0.21/RESET_24") (pintype "passive+no_connect"))
    )
    (net (code "70") (name "unconnected-(U2-P0.24-Pad29)") (class "Default")
      (node (ref "U2") (pin "29") (pinfunction "P0.24_29") (pintype "passive+no_connect"))
    )
    (net (code "71") (name "unconnected-(U2-P0.25-Pad37)") (class "Default")
      (node (ref "U2") (pin "37") (pinfunction "P0.25_37") (pintype "passive+no_connect"))
    )
    (net (code "72") (name "unconnected-(U2-P0.26-Pad38)") (class "Default")
      (node (ref "U2") (pin "38") (pinfunction "P0.26_38") (pintype "passive+no_connect"))
    )
    (net (code "73") (name "unconnected-(U2-P0.27-Pad39)") (class "Default")
      (node (ref "U2") (pin "39") (pinfunction "P0.27_39") (pintype "passive+no_connect"))
    )
    (net (code "74") (name "unconnected-(U2-P0.28{slash}AIN4-Pad40)") (class "Default")
      (node (ref "U2") (pin "40") (pinfunction "P0.28/AIN4_40") (pintype "passive+no_connect"))
    )
    (net (code "75") (name "unconnected-(U2-P0.31{slash}AIN7-Pad43)") (class "Default")
      (node (ref "U2") (pin "43") (pinfunction "P0.31/AIN7_43") (pintype "passive+no_connect"))
    )
    (net (code "76") (name "unconnected-(U4-INT2-Pad9)") (class "Default")
      (node (ref "U4") (pin "9") (pinfunction "INT2_9") (pintype "passive+no_connect"))
    )
    (net (code "77") (name "unconnected-(U4-NC-Pad10)") (class "Default")
      (node (ref "U4") (pin "10") (pinfunction "NC_10") (pintype "passive+no_connect"))
    )
    (net (code "78") (name "unconnected-(U4-NC-Pad11)") (class "Default")
      (node (ref "U4") (pin "11") (pinfunction "NC_11") (pintype "passive+no_connect"))
    )
  )
)
